# Logic_Level_Bidirectional.net
KiCad netlist of a schematic drawn in EAGLE
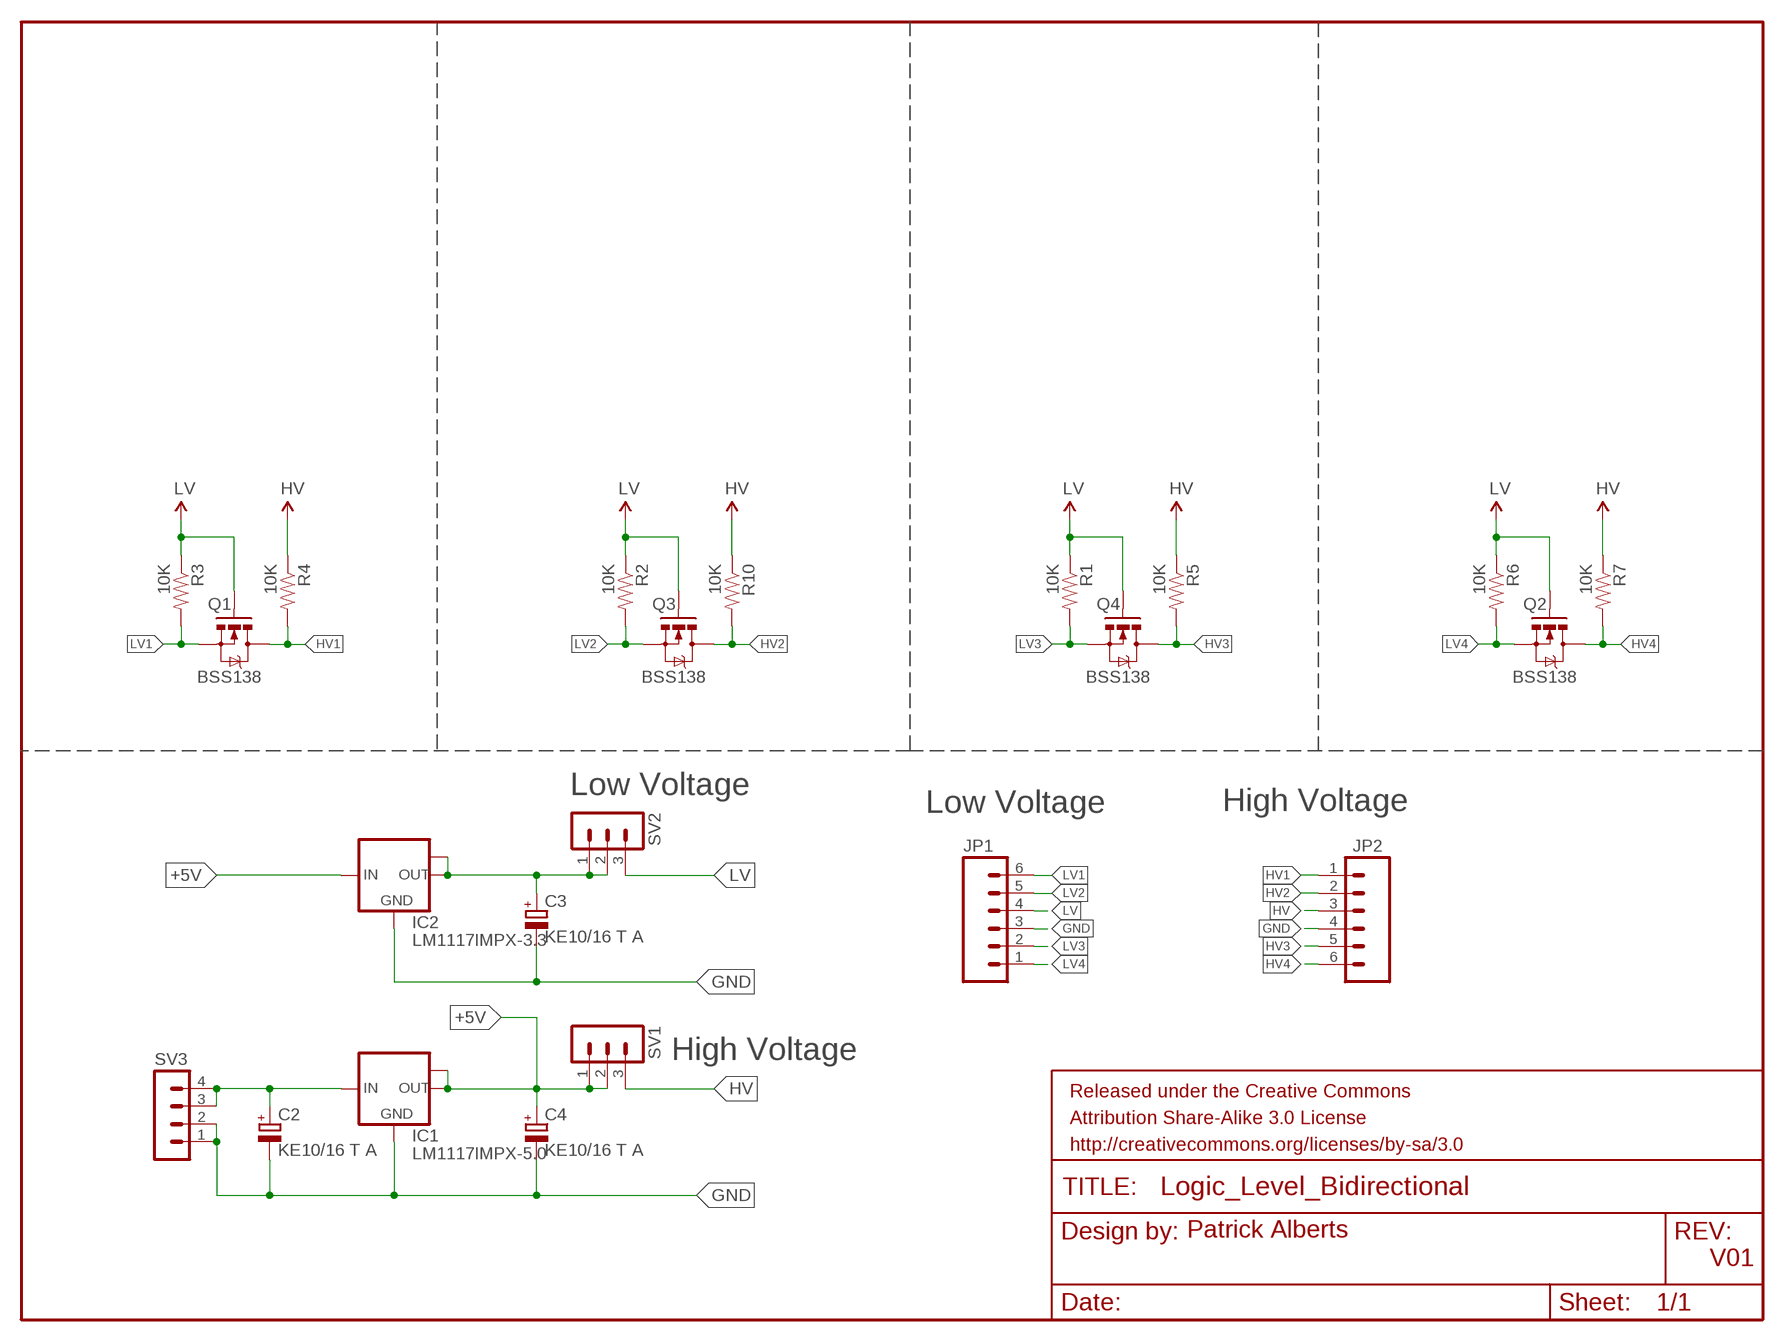
[diagram p0: schematic, sheet 1]

(export (version "E")
  (design (tool "Eeschema 10.0.6"))
  (components
    (comp (ref "C2")
      (value "KE10/16 T A")
      (footprint "eagle-import:SMC_A")
      (libsource (lib "eagle-import") (part "CPOL-EUSMCA"))
    )
    (comp (ref "C3")
      (value "KE10/16 T A")
      (footprint "eagle-import:SMC_A")
      (libsource (lib "eagle-import") (part "CPOL-EUSMCA"))
    )
    (comp (ref "C4")
      (value "KE10/16 T A")
      (footprint "eagle-import:SMC_A")
      (libsource (lib "eagle-import") (part "CPOL-EUSMCA"))
    )
    (comp (ref "IC1")
      (value "LM1117IMPX-5.0")
      (footprint "eagle-import:SOT223")
      (libsource (lib "eagle-import") (part "LM1117IMPX-5.0"))
    )
    (comp (ref "IC2")
      (value "LM1117IMPX-3.3")
      (footprint "eagle-import:SOT223")
      (libsource (lib "eagle-import") (part "LM1117IMPX-3.3"))
    )
    (comp (ref "JP1")
      (value "M06SIP")
      (footprint "eagle-import:1X06")
      (libsource (lib "eagle-import") (part "M06SIP"))
    )
    (comp (ref "JP2")
      (value "M06SIP")
      (footprint "eagle-import:1X06")
      (libsource (lib "eagle-import") (part "M06SIP"))
    )
    (comp (ref "Q1")
      (value "BSS138")
      (footprint "eagle-import:SOT23-3")
      (libsource (lib "eagle-import") (part "MOSFET-NCHANNELSMD"))
    )
    (comp (ref "Q2")
      (value "BSS138")
      (footprint "eagle-import:SOT23-3")
      (libsource (lib "eagle-import") (part "MOSFET-NCHANNELSMD"))
    )
    (comp (ref "Q3")
      (value "BSS138")
      (footprint "eagle-import:SOT23-3")
      (libsource (lib "eagle-import") (part "MOSFET-NCHANNELSMD"))
    )
    (comp (ref "Q4")
      (value "BSS138")
      (footprint "eagle-import:SOT23-3")
      (libsource (lib "eagle-import") (part "MOSFET-NCHANNELSMD"))
    )
    (comp (ref "R1")
      (value "10K")
      (footprint "eagle-import:0603-RES")
      (libsource (lib "eagle-import") (part "RESISTOR0603-RES"))
    )
    (comp (ref "R2")
      (value "10K")
      (footprint "eagle-import:0603-RES")
      (libsource (lib "eagle-import") (part "RESISTOR0603-RES"))
    )
    (comp (ref "R3")
      (value "10K")
      (footprint "eagle-import:0603-RES")
      (libsource (lib "eagle-import") (part "RESISTOR0603-RES"))
    )
    (comp (ref "R4")
      (value "10K")
      (footprint "eagle-import:0603-RES")
      (libsource (lib "eagle-import") (part "RESISTOR0603-RES"))
    )
    (comp (ref "R5")
      (value "10K")
      (footprint "eagle-import:0603-RES")
      (libsource (lib "eagle-import") (part "RESISTOR0603-RES"))
    )
    (comp (ref "R6")
      (value "10K")
      (footprint "eagle-import:0603-RES")
      (libsource (lib "eagle-import") (part "RESISTOR0603-RES"))
    )
    (comp (ref "R7")
      (value "10K")
      (footprint "eagle-import:0603-RES")
      (libsource (lib "eagle-import") (part "RESISTOR0603-RES"))
    )
    (comp (ref "R10")
      (value "10K")
      (footprint "eagle-import:0603-RES")
      (libsource (lib "eagle-import") (part "RESISTOR0603-RES"))
    )
    (comp (ref "SV1")
      (value "MA03-1")
      (footprint "eagle-import:MA03-1")
      (libsource (lib "eagle-import") (part "MA03-1"))
    )
    (comp (ref "SV2")
      (value "MA03-1")
      (footprint "eagle-import:MA03-1")
      (libsource (lib "eagle-import") (part "MA03-1"))
    )
    (comp (ref "SV3")
      (value "MA04-1")
      (footprint "eagle-import:MA04-1")
      (libsource (lib "eagle-import") (part "MA04-1"))
    )
  )
  (nets
    (net (code "1") (name "+5V") (class "Default")
      (node (ref "C4") (pin "+") (pinfunction "+_+") (pintype "passive"))
      (node (ref "IC1") (pin "2") (pinfunction "OUT_2") (pintype "passive"))
      (node (ref "IC1") (pin "TAB") (pinfunction "OUT1_TAB") (pintype "passive"))
      (node (ref "IC2") (pin "3") (pinfunction "IN_3") (pintype "input"))
      (node (ref "SV1") (pin "1") (pinfunction "1_1") (pintype "passive"))
      (node (ref "SV1") (pin "2") (pinfunction "2_2") (pintype "passive"))
    )
    (net (code "2") (name "GND") (class "Default")
      (node (ref "C2") (pin "-") (pinfunction "-_-") (pintype "passive"))
      (node (ref "C3") (pin "-") (pinfunction "-_-") (pintype "passive"))
      (node (ref "C4") (pin "-") (pinfunction "-_-") (pintype "passive"))
      (node (ref "IC1") (pin "1") (pinfunction "GND_1") (pintype "input"))
      (node (ref "IC2") (pin "1") (pinfunction "GND_1") (pintype "input"))
      (node (ref "JP1") (pin "3") (pinfunction "3_3") (pintype "passive"))
      (node (ref "JP2") (pin "4") (pinfunction "4_4") (pintype "passive"))
      (node (ref "SV3") (pin "1") (pinfunction "1_1") (pintype "passive"))
      (node (ref "SV3") (pin "2") (pinfunction "2_2") (pintype "passive"))
    )
    (net (code "3") (name "HV") (class "Default")
      (node (ref "JP2") (pin "3") (pinfunction "3_3") (pintype "passive"))
      (node (ref "R10") (pin "1") (pinfunction "1_1") (pintype "passive"))
      (node (ref "R4") (pin "1") (pinfunction "1_1") (pintype "passive"))
      (node (ref "R5") (pin "1") (pinfunction "1_1") (pintype "passive"))
      (node (ref "R7") (pin "1") (pinfunction "1_1") (pintype "passive"))
      (node (ref "SV1") (pin "3") (pinfunction "3_3") (pintype "passive"))
    )
    (net (code "4") (name "HV1") (class "Default")
      (node (ref "JP2") (pin "1") (pinfunction "1_1") (pintype "passive"))
      (node (ref "Q1") (pin "3") (pinfunction "D_3") (pintype "passive"))
      (node (ref "R4") (pin "2") (pinfunction "2_2") (pintype "passive"))
    )
    (net (code "5") (name "HV2") (class "Default")
      (node (ref "JP2") (pin "2") (pinfunction "2_2") (pintype "passive"))
      (node (ref "Q3") (pin "3") (pinfunction "D_3") (pintype "passive"))
      (node (ref "R10") (pin "2") (pinfunction "2_2") (pintype "passive"))
    )
    (net (code "6") (name "HV3") (class "Default")
      (node (ref "JP2") (pin "5") (pinfunction "5_5") (pintype "passive"))
      (node (ref "Q4") (pin "3") (pinfunction "D_3") (pintype "passive"))
      (node (ref "R5") (pin "2") (pinfunction "2_2") (pintype "passive"))
    )
    (net (code "7") (name "HV4") (class "Default")
      (node (ref "JP2") (pin "6") (pinfunction "6_6") (pintype "passive"))
      (node (ref "Q2") (pin "3") (pinfunction "D_3") (pintype "passive"))
      (node (ref "R7") (pin "2") (pinfunction "2_2") (pintype "passive"))
    )
    (net (code "8") (name "LV") (class "Default")
      (node (ref "JP1") (pin "4") (pinfunction "4_4") (pintype "passive"))
      (node (ref "Q1") (pin "1") (pinfunction "G_1") (pintype "passive"))
      (node (ref "Q2") (pin "1") (pinfunction "G_1") (pintype "passive"))
      (node (ref "Q3") (pin "1") (pinfunction "G_1") (pintype "passive"))
      (node (ref "Q4") (pin "1") (pinfunction "G_1") (pintype "passive"))
      (node (ref "R1") (pin "1") (pinfunction "1_1") (pintype "passive"))
      (node (ref "R2") (pin "1") (pinfunction "1_1") (pintype "passive"))
      (node (ref "R3") (pin "1") (pinfunction "1_1") (pintype "passive"))
      (node (ref "R6") (pin "1") (pinfunction "1_1") (pintype "passive"))
      (node (ref "SV2") (pin "3") (pinfunction "3_3") (pintype "passive"))
    )
    (net (code "9") (name "LV1") (class "Default")
      (node (ref "JP1") (pin "6") (pinfunction "6_6") (pintype "passive"))
      (node (ref "Q1") (pin "2") (pinfunction "S_2") (pintype "passive"))
      (node (ref "R3") (pin "2") (pinfunction "2_2") (pintype "passive"))
    )
    (net (code "10") (name "LV2") (class "Default")
      (node (ref "JP1") (pin "5") (pinfunction "5_5") (pintype "passive"))
      (node (ref "Q3") (pin "2") (pinfunction "S_2") (pintype "passive"))
      (node (ref "R2") (pin "2") (pinfunction "2_2") (pintype "passive"))
    )
    (net (code "11") (name "LV3") (class "Default")
      (node (ref "JP1") (pin "2") (pinfunction "2_2") (pintype "passive"))
      (node (ref "Q4") (pin "2") (pinfunction "S_2") (pintype "passive"))
      (node (ref "R1") (pin "2") (pinfunction "2_2") (pintype "passive"))
    )
    (net (code "12") (name "LV4") (class "Default")
      (node (ref "JP1") (pin "1") (pinfunction "1_1") (pintype "passive"))
      (node (ref "Q2") (pin "2") (pinfunction "S_2") (pintype "passive"))
      (node (ref "R6") (pin "2") (pinfunction "2_2") (pintype "passive"))
    )
    (net (code "13") (name "Net-(IC1-IN)") (class "Default")
      (node (ref "C2") (pin "+") (pinfunction "+_+") (pintype "passive"))
      (node (ref "IC1") (pin "3") (pinfunction "IN_3") (pintype "input"))
      (node (ref "SV3") (pin "3") (pinfunction "3_3") (pintype "passive"))
      (node (ref "SV3") (pin "4") (pinfunction "4_4") (pintype "passive"))
    )
    (net (code "14") (name "Net-(IC2-OUT)") (class "Default")
      (node (ref "C3") (pin "+") (pinfunction "+_+") (pintype "passive"))
      (node (ref "IC2") (pin "2") (pinfunction "OUT_2") (pintype "passive"))
      (node (ref "IC2") (pin "TAB") (pinfunction "OUT1_TAB") (pintype "passive"))
      (node (ref "SV2") (pin "1") (pinfunction "1_1") (pintype "passive"))
      (node (ref "SV2") (pin "2") (pinfunction "2_2") (pintype "passive"))
    )
  )
)
